# thermostat_sensor_esp32.net
KiCad netlist of a schematic drawn in EAGLE
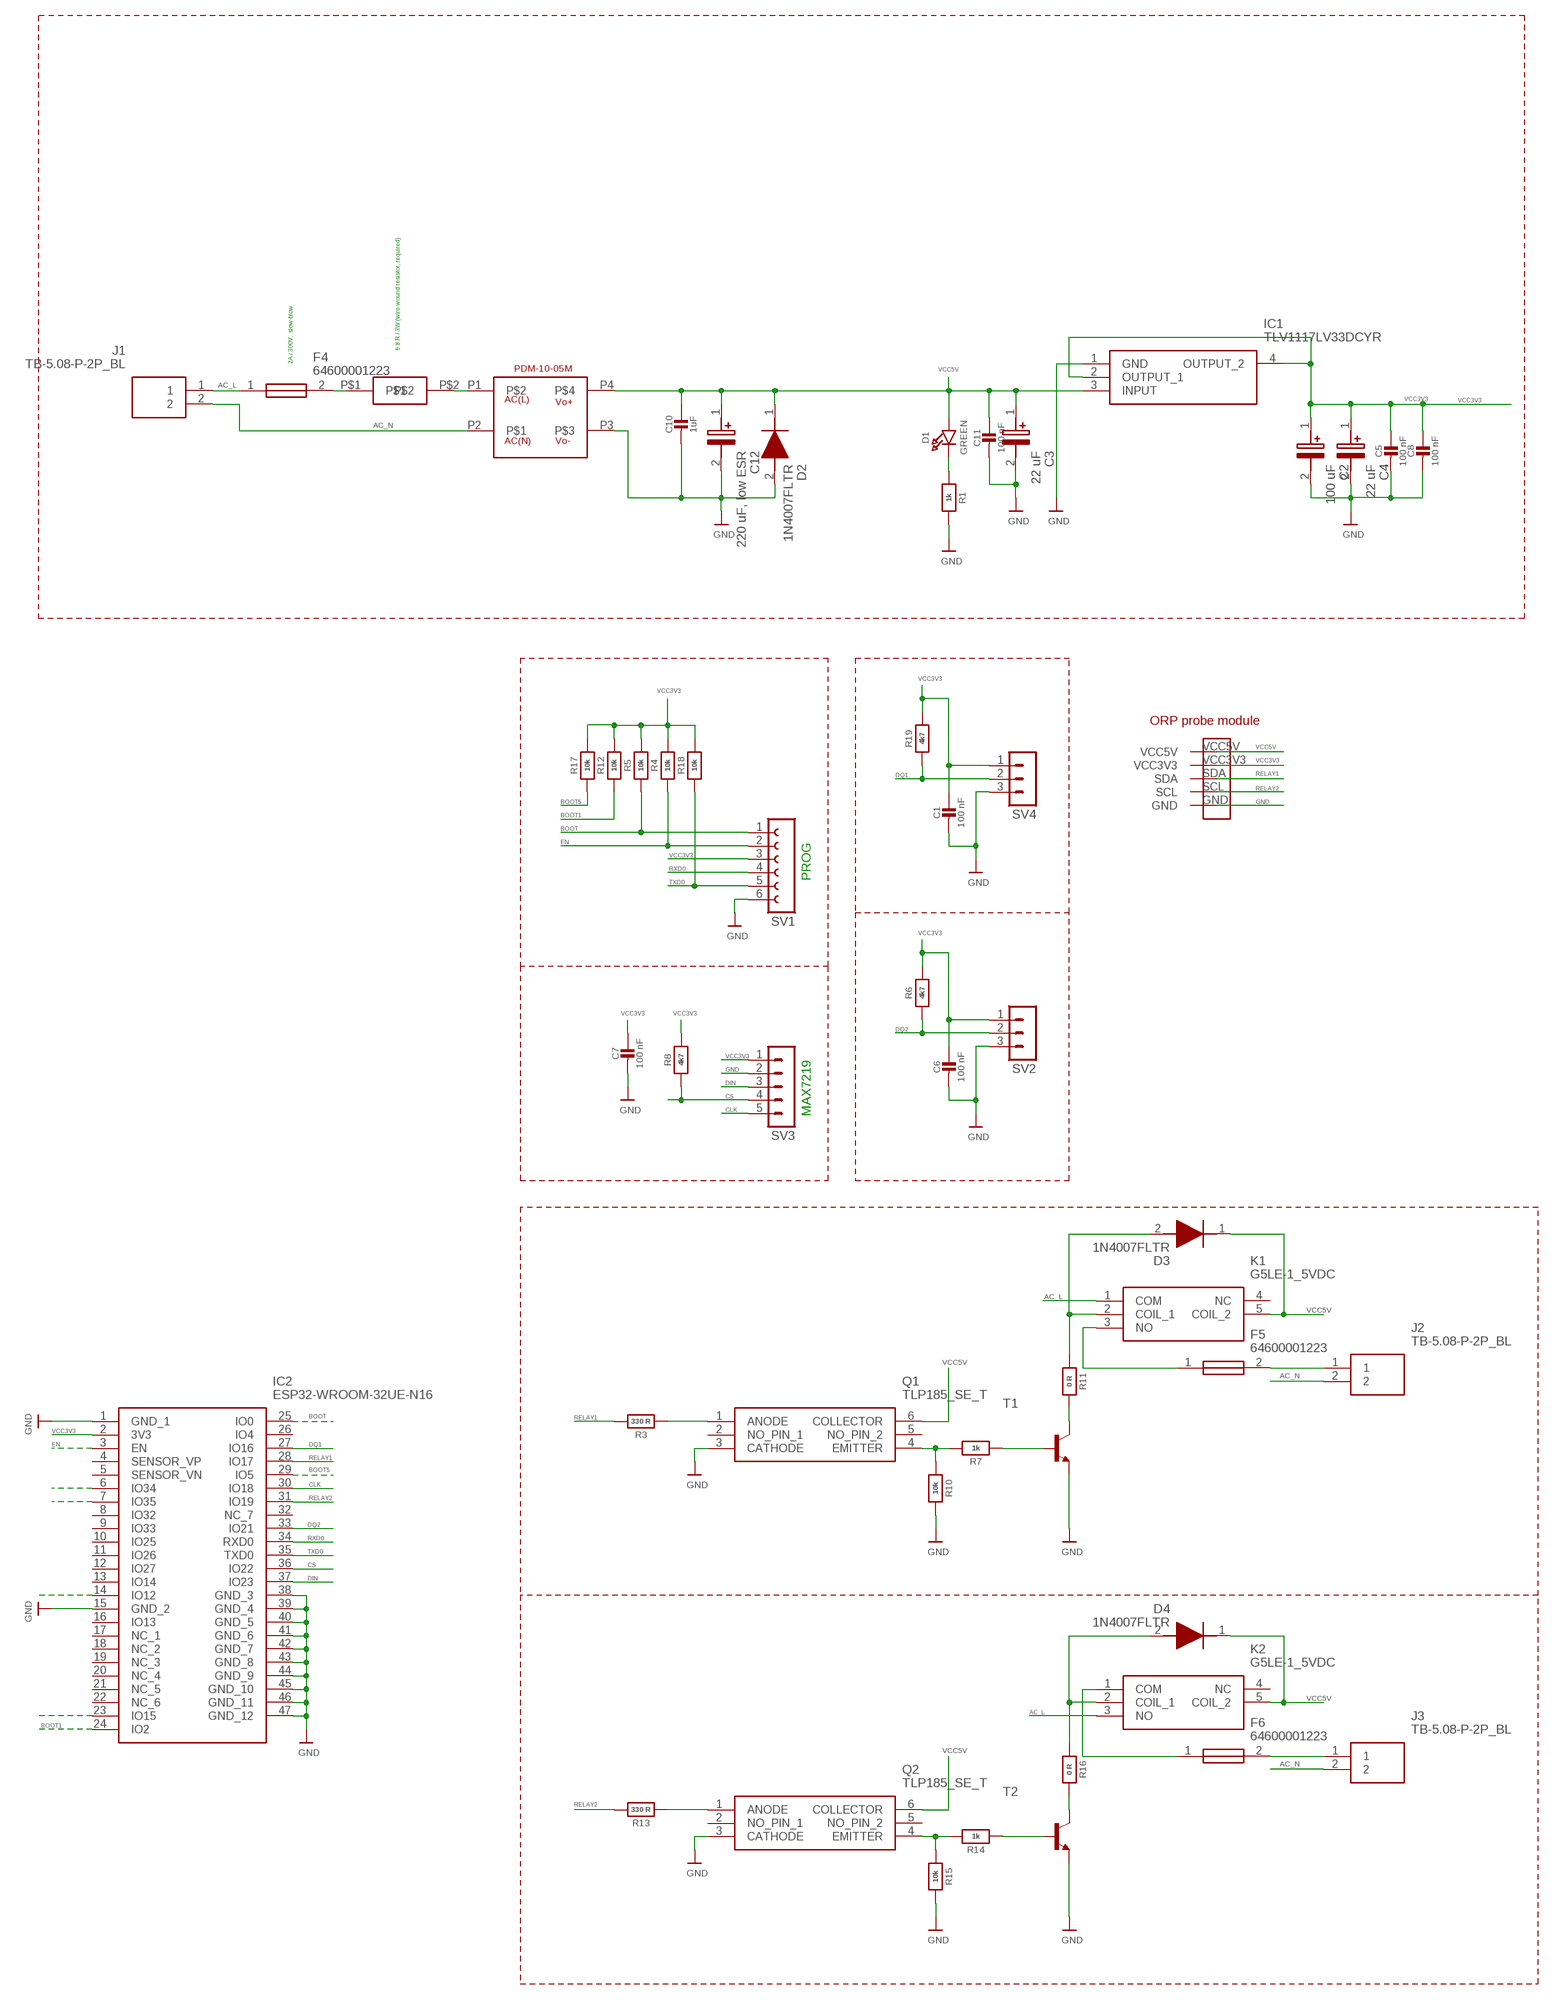
[diagram p0: schematic, sheet 1]

(export (version "E")
  (design (tool "Eeschema 10.0.6"))
  (components
    (comp (ref "C1")
      (value "100 nF")
      (footprint "eagle-import:_0603")
      (libsource (lib "eagle-import") (part "CAP_CERAMIC_0603"))
    )
    (comp (ref "C2")
      (value "100 uF")
      (footprint "eagle-import:CAPPM6032X280N")
      (fields (field (name "MANUFACTURER_PART_NUMBER") "293D107X9010C2TE3"))
      (libsource (lib "eagle-import") (part "293D107X9010C2TE3"))
    )
    (comp (ref "C3")
      (value "22 uF")
      (footprint "eagle-import:CAPPM3216X180N")
      (description "Solid Tantalum Surface Mount Chip Capacitors TANTAMOUNT(TM), Molded Case, Standard Industrial Grade")
      (fields
        (field (name "MANUFACTURER_PART_NUMBER") "293D226X9010A2TE3")
        (field (name "HEIGHT") "1.8mm")
        (field (name "MANUFACTURER_NAME") "Vishay")
        (field (name "MANUFACTURER_PART_NUMBER_1") "293D226X9010A2TE3")
      )
      (libsource (lib "eagle-import") (part "293D226X9010A2TE3"))
    )
    (comp (ref "C4")
      (value "22 uF")
      (footprint "eagle-import:CAPPM3216X180N")
      (description "Solid Tantalum Surface Mount Chip Capacitors TANTAMOUNT(TM), Molded Case, Standard Industrial Grade")
      (fields
        (field (name "MANUFACTURER_PART_NUMBER") "293D226X9010A2TE3")
        (field (name "HEIGHT") "1.8mm")
        (field (name "MANUFACTURER_NAME") "Vishay")
        (field (name "MANUFACTURER_PART_NUMBER_1") "293D226X9010A2TE3")
      )
      (libsource (lib "eagle-import") (part "293D226X9010A2TE3"))
    )
    (comp (ref "C5")
      (value "100 nF")
      (footprint "eagle-import:_0603")
      (libsource (lib "eagle-import") (part "CAP_CERAMIC_0603"))
    )
    (comp (ref "C6")
      (value "100 nF")
      (footprint "eagle-import:_0603")
      (libsource (lib "eagle-import") (part "CAP_CERAMIC_0603"))
    )
    (comp (ref "C7")
      (value "100 nF")
      (footprint "eagle-import:_0603")
      (libsource (lib "eagle-import") (part "CAP_CERAMIC_0603"))
    )
    (comp (ref "C8")
      (value "100 nF")
      (footprint "eagle-import:_0603")
      (libsource (lib "eagle-import") (part "CAP_CERAMIC_0603"))
    )
    (comp (ref "C10")
      (value "1uF")
      (footprint "eagle-import:0805-NO")
      (libsource (lib "eagle-import") (part "CAP_CERAMIC0805-NOOUTLINE"))
    )
    (comp (ref "C11")
      (value "100 nF")
      (footprint "eagle-import:_0603")
      (libsource (lib "eagle-import") (part "CAP_CERAMIC_0603"))
    )
    (comp (ref "C12")
      (value "220 uF, low ESR")
      (footprint "eagle-import:CAPPRD350W65D800H1300")
      (fields (field (name "MANUFACTURER_PART_NUMBER") "EEUFR1E221B"))
      (libsource (lib "eagle-import") (part "EEUFR1E221B"))
    )
    (comp (ref "D1")
      (value "GREEN")
      (footprint "eagle-import:CHIPLED_0805_NOOUTLINE")
      (libsource (lib "eagle-import") (part "LED0805_NOOUTLINE"))
    )
    (comp (ref "D2")
      (value "1N4007FLTR")
      (footprint "eagle-import:SODFL3718X140N")
      (libsource (lib "eagle-import") (part "1N4007FLTR"))
    )
    (comp (ref "D3")
      (value "1N4007FLTR")
      (footprint "eagle-import:SODFL3718X140N")
      (description "General Purpose Plastic Rectifier")
      (fields
        (field (name "HEIGHT") "1.4mm")
        (field (name "MANUFACTURER_NAME") "SMC Diode Solutions")
        (field (name "MANUFACTURER_PART_NUMBER") "1N4007FLTR")
      )
      (libsource (lib "eagle-import") (part "1N4007FLTR"))
    )
    (comp (ref "D4")
      (value "1N4007FLTR")
      (footprint "eagle-import:SODFL3718X140N")
      (description "General Purpose Plastic Rectifier")
      (fields
        (field (name "HEIGHT") "1.4mm")
        (field (name "MANUFACTURER_NAME") "SMC Diode Solutions")
        (field (name "MANUFACTURER_PART_NUMBER") "1N4007FLTR")
      )
      (libsource (lib "eagle-import") (part "1N4007FLTR"))
    )
    (comp (ref "F4")
      (value "64600001223")
      (footprint "eagle-import:64600001223")
      (libsource (lib "eagle-import") (part "64600001223"))
    )
    (comp (ref "F5")
      (value "64600001223")
      (footprint "eagle-import:64600001223")
      (libsource (lib "eagle-import") (part "64600001223"))
    )
    (comp (ref "F6")
      (value "64600001223")
      (footprint "eagle-import:64600001223")
      (libsource (lib "eagle-import") (part "64600001223"))
    )
    (comp (ref "IC1")
      (value "TLV1117LV33DCYR")
      (footprint "eagle-import:SOT230P700X180-4N")
      (libsource (lib "eagle-import") (part "TLV1117LV33DCYR"))
    )
    (comp (ref "IC2")
      (value "ESP32-WROOM-32UE-N16")
      (footprint "eagle-import:ESP32WROOM32UEN16")
      (libsource (lib "eagle-import") (part "ESP32-WROOM-32UE-N16"))
    )
    (comp (ref "J1")
      (value "TB-5.08-P-2P_BL")
      (footprint "eagle-import:TB508P2PBL")
      (fields (field (name "MANUFACTURER_PART_NUMBER") "TB-5.08-P-2P/BL"))
      (libsource (lib "eagle-import") (part "TB-5.08-P-2P_BL"))
    )
    (comp (ref "J2")
      (value "TB-5.08-P-2P_BL")
      (footprint "eagle-import:TB508P2PBL")
      (description "PCB terminal block; angled 90; 5.08mm; ways: 2; on PCBs; 1.5mm2")
      (fields
        (field (name "MANUFACTURER_PART_NUMBER") "TB-5.08-P-2P/BL")
        (field (name "HEIGHT") "10mm")
        (field (name "MANUFACTURER_NAME") "Ninigi")
        (field (name "MANUFACTURER_PART_NUMBER_1") "TB-5.08-P-2P/BL")
      )
      (libsource (lib "eagle-import") (part "TB-5.08-P-2P_BL"))
    )
    (comp (ref "J3")
      (value "TB-5.08-P-2P_BL")
      (footprint "eagle-import:TB508P2PBL")
      (description "PCB terminal block; angled 90; 5.08mm; ways: 2; on PCBs; 1.5mm2")
      (fields
        (field (name "MANUFACTURER_PART_NUMBER") "TB-5.08-P-2P/BL")
        (field (name "HEIGHT") "10mm")
        (field (name "MANUFACTURER_NAME") "Ninigi")
        (field (name "MANUFACTURER_PART_NUMBER_1") "TB-5.08-P-2P/BL")
      )
      (libsource (lib "eagle-import") (part "TB-5.08-P-2P_BL"))
    )
    (comp (ref "K1")
      (value "G5LE-1_5VDC")
      (footprint "eagle-import:G5LE15VDC")
      (fields (field (name "MANUFACTURER_PART_NUMBER") "G5LE-1 5VDC"))
      (libsource (lib "eagle-import") (part "G5LE-1_5VDC"))
    )
    (comp (ref "K2")
      (value "G5LE-1_5VDC")
      (footprint "eagle-import:G5LE15VDC")
      (fields (field (name "MANUFACTURER_PART_NUMBER") "G5LE-1 5VDC"))
      (libsource (lib "eagle-import") (part "G5LE-1_5VDC"))
    )
    (comp (ref "Q1")
      (value "TLP185_SE_T")
      (footprint "eagle-import:SOIC127P700X230-6N")
      (fields (field (name "MANUFACTURER_PART_NUMBER") "TLP185(SE(T"))
      (libsource (lib "eagle-import") (part "TLP185_SE_T"))
    )
    (comp (ref "Q2")
      (value "TLP185_SE_T")
      (footprint "eagle-import:SOIC127P700X230-6N")
      (fields (field (name "MANUFACTURER_PART_NUMBER") "TLP185(SE(T"))
      (libsource (lib "eagle-import") (part "TLP185_SE_T"))
    )
    (comp (ref "R1")
      (value "1k")
      (footprint "eagle-import:_0603")
      (libsource (lib "eagle-import") (part "RESISTOR_0603"))
    )
    (comp (ref "R3")
      (value "330 R")
      (footprint "eagle-import:_0603")
      (libsource (lib "eagle-import") (part "RESISTOR_0603"))
    )
    (comp (ref "R4")
      (value "10k")
      (footprint "eagle-import:_0603")
      (libsource (lib "eagle-import") (part "RESISTOR_0603"))
    )
    (comp (ref "R5")
      (value "10k")
      (footprint "eagle-import:_0603")
      (libsource (lib "eagle-import") (part "RESISTOR_0603"))
    )
    (comp (ref "R6")
      (value "4k7")
      (footprint "eagle-import:_0603")
      (libsource (lib "eagle-import") (part "RESISTOR_0603"))
    )
    (comp (ref "R7")
      (value "1k")
      (footprint "eagle-import:_0603")
      (libsource (lib "eagle-import") (part "RESISTOR_0603"))
    )
    (comp (ref "R8")
      (value "4k7")
      (footprint "eagle-import:_0603")
      (libsource (lib "eagle-import") (part "RESISTOR_0603"))
    )
    (comp (ref "R10")
      (value "10k")
      (footprint "eagle-import:_0603")
      (libsource (lib "eagle-import") (part "RESISTOR_0603"))
    )
    (comp (ref "R11")
      (value "0 R")
      (footprint "eagle-import:_0603")
      (libsource (lib "eagle-import") (part "RESISTOR_0603"))
    )
    (comp (ref "R12")
      (value "10k")
      (footprint "eagle-import:_0603")
      (libsource (lib "eagle-import") (part "RESISTOR_0603"))
    )
    (comp (ref "R13")
      (value "330 R")
      (footprint "eagle-import:_0603")
      (libsource (lib "eagle-import") (part "RESISTOR_0603"))
    )
    (comp (ref "R14")
      (value "1k")
      (footprint "eagle-import:_0603")
      (libsource (lib "eagle-import") (part "RESISTOR_0603"))
    )
    (comp (ref "R15")
      (value "10k")
      (footprint "eagle-import:_0603")
      (libsource (lib "eagle-import") (part "RESISTOR_0603"))
    )
    (comp (ref "R16")
      (value "0 R")
      (footprint "eagle-import:_0603")
      (libsource (lib "eagle-import") (part "RESISTOR_0603"))
    )
    (comp (ref "R17")
      (value "10k")
      (footprint "eagle-import:_0603")
      (libsource (lib "eagle-import") (part "RESISTOR_0603"))
    )
    (comp (ref "R18")
      (value "10k")
      (footprint "eagle-import:_0603")
      (libsource (lib "eagle-import") (part "RESISTOR_0603"))
    )
    (comp (ref "R19")
      (value "4k7")
      (footprint "eagle-import:_0603")
      (libsource (lib "eagle-import") (part "RESISTOR_0603"))
    )
    (comp (ref "SV1")
      (value "FE06-1")
      (footprint "eagle-import:FE06")
      (libsource (lib "eagle-import") (part "FE06-1"))
    )
    (comp (ref "SV2")
      (value "MA03-1")
      (footprint "eagle-import:MA03-1")
      (libsource (lib "eagle-import") (part "MA03-1"))
    )
    (comp (ref "SV3")
      (value "MA05-1")
      (footprint "eagle-import:MA05-1")
      (libsource (lib "eagle-import") (part "MA05-1"))
    )
    (comp (ref "SV4")
      (value "MA03-1")
      (footprint "eagle-import:MA03-1")
      (libsource (lib "eagle-import") (part "MA03-1"))
    )
    (comp (ref "T1")
      (value "BC817-16-NPN-SOT23-BEC")
      (footprint "eagle-import:SOT23-BEC")
      (libsource (lib "eagle-import") (part "-NPN-SOT23-BECBC817-16"))
    )
    (comp (ref "T2")
      (value "BC817-16-NPN-SOT23-BEC")
      (footprint "eagle-import:SOT23-BEC")
      (libsource (lib "eagle-import") (part "-NPN-SOT23-BECBC817-16"))
    )
    (comp (ref "U$1")
      (value "PDM-10-05M")
      (footprint "eagle-import:PDM-10-05M")
      (libsource (lib "eagle-import") (part "PDM-10-05M"))
    )
    (comp (ref "U$20")
      (value "6.8 R / 3W (wire-wound resistor, required)")
      (footprint "eagle-import:R_HIGH_POWER")
      (libsource (lib "eagle-import") (part "R_HIGH_POWER"))
    )
    (comp (ref "U$21")
      (value "ORP_PROBE")
      (footprint "eagle-import:ORP_PROBE")
      (libsource (lib "eagle-import") (part "ORP_PROBE"))
    )
  )
  (nets
    (net (code "1") (name "/AC_L") (class "Default")
      (node (ref "F4") (pin "1") (pinfunction "1_1") (pintype "bidirectional"))
      (node (ref "J1") (pin "1") (pinfunction "1_1") (pintype "bidirectional"))
      (node (ref "K1") (pin "1") (pinfunction "COM_1") (pintype "bidirectional"))
      (node (ref "K2") (pin "3") (pinfunction "NO_3") (pintype "bidirectional"))
    )
    (net (code "2") (name "/AC_N") (class "Default")
      (node (ref "J1") (pin "2") (pinfunction "2_2") (pintype "bidirectional"))
      (node (ref "J2") (pin "2") (pinfunction "2_2") (pintype "bidirectional"))
      (node (ref "J3") (pin "2") (pinfunction "2_2") (pintype "bidirectional"))
      (node (ref "U$1") (pin "P2") (pinfunction "P$1_P2") (pintype "bidirectional"))
    )
    (net (code "3") (name "/BOOT") (class "Default")
      (node (ref "IC2") (pin "25") (pinfunction "IO0_25") (pintype "bidirectional"))
      (node (ref "R5") (pin "1") (pinfunction "1_1") (pintype "passive"))
      (node (ref "SV1") (pin "1") (pinfunction "1_1") (pintype "passive"))
    )
    (net (code "4") (name "/BOOT1") (class "Default")
      (node (ref "IC2") (pin "24") (pinfunction "IO2_24") (pintype "bidirectional"))
      (node (ref "R12") (pin "1") (pinfunction "1_1") (pintype "passive"))
    )
    (net (code "5") (name "/BOOT5") (class "Default")
      (node (ref "IC2") (pin "29") (pinfunction "IO5_29") (pintype "bidirectional"))
      (node (ref "R17") (pin "1") (pinfunction "1_1") (pintype "passive"))
    )
    (net (code "6") (name "/CLK") (class "Default")
      (node (ref "IC2") (pin "30") (pinfunction "IO18_30") (pintype "bidirectional"))
      (node (ref "SV3") (pin "5") (pinfunction "5_5") (pintype "passive"))
    )
    (net (code "7") (name "/CS") (class "Default")
      (node (ref "IC2") (pin "36") (pinfunction "IO22_36") (pintype "bidirectional"))
      (node (ref "R8") (pin "1") (pinfunction "1_1") (pintype "passive"))
      (node (ref "SV3") (pin "4") (pinfunction "4_4") (pintype "passive"))
    )
    (net (code "8") (name "/DIN") (class "Default")
      (node (ref "IC2") (pin "37") (pinfunction "IO23_37") (pintype "bidirectional"))
      (node (ref "SV3") (pin "3") (pinfunction "3_3") (pintype "passive"))
    )
    (net (code "9") (name "/DQ1") (class "Default")
      (node (ref "IC2") (pin "27") (pinfunction "IO16_27") (pintype "bidirectional"))
      (node (ref "R19") (pin "1") (pinfunction "1_1") (pintype "passive"))
      (node (ref "SV4") (pin "2") (pinfunction "2_2") (pintype "passive"))
    )
    (net (code "10") (name "/DQ2") (class "Default")
      (node (ref "IC2") (pin "33") (pinfunction "IO21_33") (pintype "bidirectional"))
      (node (ref "R6") (pin "1") (pinfunction "1_1") (pintype "passive"))
      (node (ref "SV2") (pin "2") (pinfunction "2_2") (pintype "passive"))
    )
    (net (code "11") (name "/EN") (class "Default")
      (node (ref "IC2") (pin "3") (pinfunction "EN_3") (pintype "bidirectional"))
      (node (ref "R4") (pin "1") (pinfunction "1_1") (pintype "passive"))
      (node (ref "SV1") (pin "2") (pinfunction "2_2") (pintype "passive"))
    )
    (net (code "12") (name "/RELAY1") (class "Default")
      (node (ref "IC2") (pin "28") (pinfunction "IO17_28") (pintype "bidirectional"))
      (node (ref "R3") (pin "2") (pinfunction "2_2") (pintype "passive"))
      (node (ref "U$21") (pin "SDA") (pinfunction "SDA_SDA") (pintype "bidirectional"))
    )
    (net (code "13") (name "/RELAY2") (class "Default")
      (node (ref "IC2") (pin "31") (pinfunction "IO19_31") (pintype "bidirectional"))
      (node (ref "R13") (pin "2") (pinfunction "2_2") (pintype "passive"))
      (node (ref "U$21") (pin "SCL") (pinfunction "SCL_SCL") (pintype "bidirectional"))
    )
    (net (code "14") (name "/RXD0") (class "Default")
      (node (ref "IC2") (pin "34") (pinfunction "RXD0_34") (pintype "bidirectional"))
      (node (ref "SV1") (pin "4") (pinfunction "4_4") (pintype "passive"))
    )
    (net (code "15") (name "/TXD0") (class "Default")
      (node (ref "IC2") (pin "35") (pinfunction "TXD0_35") (pintype "bidirectional"))
      (node (ref "R18") (pin "1") (pinfunction "1_1") (pintype "passive"))
      (node (ref "SV1") (pin "5") (pinfunction "5_5") (pintype "passive"))
    )
    (net (code "16") (name "/VCC3V3") (class "Default")
      (node (ref "C1") (pin "1") (pinfunction "1_1") (pintype "passive"))
      (node (ref "C2") (pin "1") (pinfunction "+_1") (pintype "bidirectional"))
      (node (ref "C4") (pin "1") (pinfunction "+_1") (pintype "bidirectional"))
      (node (ref "C5") (pin "1") (pinfunction "1_1") (pintype "passive"))
      (node (ref "C6") (pin "1") (pinfunction "1_1") (pintype "passive"))
      (node (ref "C7") (pin "1") (pinfunction "1_1") (pintype "passive"))
      (node (ref "C8") (pin "1") (pinfunction "1_1") (pintype "passive"))
      (node (ref "IC1") (pin "2") (pinfunction "OUTPUT_1_2") (pintype "bidirectional"))
      (node (ref "IC1") (pin "4") (pinfunction "OUTPUT_2_4") (pintype "bidirectional"))
      (node (ref "IC2") (pin "2") (pinfunction "3V3_2") (pintype "bidirectional"))
      (node (ref "R12") (pin "2") (pinfunction "2_2") (pintype "passive"))
      (node (ref "R17") (pin "2") (pinfunction "2_2") (pintype "passive"))
      (node (ref "R18") (pin "2") (pinfunction "2_2") (pintype "passive"))
      (node (ref "R19") (pin "2") (pinfunction "2_2") (pintype "passive"))
      (node (ref "R4") (pin "2") (pinfunction "2_2") (pintype "passive"))
      (node (ref "R5") (pin "2") (pinfunction "2_2") (pintype "passive"))
      (node (ref "R6") (pin "2") (pinfunction "2_2") (pintype "passive"))
      (node (ref "R8") (pin "2") (pinfunction "2_2") (pintype "passive"))
      (node (ref "SV1") (pin "3") (pinfunction "3_3") (pintype "passive"))
      (node (ref "SV2") (pin "1") (pinfunction "1_1") (pintype "passive"))
      (node (ref "SV3") (pin "1") (pinfunction "1_1") (pintype "passive"))
      (node (ref "SV4") (pin "1") (pinfunction "1_1") (pintype "passive"))
      (node (ref "U$21") (pin "VCC3V3") (pinfunction "VCC3V3_VCC3V3") (pintype "bidirectional"))
    )
    (net (code "17") (name "/VCC5V") (class "Default")
      (node (ref "C10") (pin "1") (pinfunction "1_1") (pintype "passive"))
      (node (ref "C11") (pin "1") (pinfunction "1_1") (pintype "passive"))
      (node (ref "C12") (pin "1") (pinfunction "+_1") (pintype "bidirectional"))
      (node (ref "C3") (pin "1") (pinfunction "+_1") (pintype "bidirectional"))
      (node (ref "D1") (pin "A") (pinfunction "A_A") (pintype "passive"))
      (node (ref "D2") (pin "1") (pinfunction "K_1") (pintype "bidirectional"))
      (node (ref "D3") (pin "1") (pinfunction "K_1") (pintype "bidirectional"))
      (node (ref "D4") (pin "1") (pinfunction "K_1") (pintype "bidirectional"))
      (node (ref "IC1") (pin "3") (pinfunction "INPUT_3") (pintype "bidirectional"))
      (node (ref "K1") (pin "5") (pinfunction "COIL_2_5") (pintype "bidirectional"))
      (node (ref "K2") (pin "5") (pinfunction "COIL_2_5") (pintype "bidirectional"))
      (node (ref "Q1") (pin "6") (pinfunction "COLLECTOR_6") (pintype "bidirectional"))
      (node (ref "Q2") (pin "6") (pinfunction "COLLECTOR_6") (pintype "bidirectional"))
      (node (ref "U$1") (pin "P4") (pinfunction "P$4_P4") (pintype "bidirectional"))
      (node (ref "U$21") (pin "VCC5V") (pinfunction "VCC5V_VCC5V") (pintype "bidirectional"))
    )
    (net (code "18") (name "GND") (class "Default")
      (node (ref "C1") (pin "2") (pinfunction "2_2") (pintype "passive"))
      (node (ref "C10") (pin "2") (pinfunction "2_2") (pintype "passive"))
      (node (ref "C11") (pin "2") (pinfunction "2_2") (pintype "passive"))
      (node (ref "C12") (pin "2") (pinfunction "-_2") (pintype "bidirectional"))
      (node (ref "C2") (pin "2") (pinfunction "-_2") (pintype "bidirectional"))
      (node (ref "C3") (pin "2") (pinfunction "-_2") (pintype "bidirectional"))
      (node (ref "C4") (pin "2") (pinfunction "-_2") (pintype "bidirectional"))
      (node (ref "C5") (pin "2") (pinfunction "2_2") (pintype "passive"))
      (node (ref "C6") (pin "2") (pinfunction "2_2") (pintype "passive"))
      (node (ref "C7") (pin "2") (pinfunction "2_2") (pintype "passive"))
      (node (ref "C8") (pin "2") (pinfunction "2_2") (pintype "passive"))
      (node (ref "D2") (pin "2") (pinfunction "A_2") (pintype "bidirectional"))
      (node (ref "IC1") (pin "1") (pinfunction "GND_1") (pintype "bidirectional"))
      (node (ref "IC2") (pin "1") (pinfunction "GND_1_1") (pintype "bidirectional"))
      (node (ref "IC2") (pin "15") (pinfunction "GND_2_15") (pintype "bidirectional"))
      (node (ref "IC2") (pin "38") (pinfunction "GND_3_38") (pintype "bidirectional"))
      (node (ref "IC2") (pin "39") (pinfunction "GND_4_39") (pintype "bidirectional"))
      (node (ref "IC2") (pin "40") (pinfunction "GND_5_40") (pintype "bidirectional"))
      (node (ref "IC2") (pin "41") (pinfunction "GND_6_41") (pintype "bidirectional"))
      (node (ref "IC2") (pin "42") (pinfunction "GND_7_42") (pintype "bidirectional"))
      (node (ref "IC2") (pin "43") (pinfunction "GND_8_43") (pintype "bidirectional"))
      (node (ref "IC2") (pin "44") (pinfunction "GND_9_44") (pintype "bidirectional"))
      (node (ref "IC2") (pin "45") (pinfunction "GND_10_45") (pintype "bidirectional"))
      (node (ref "IC2") (pin "46") (pinfunction "GND_11_46") (pintype "bidirectional"))
      (node (ref "IC2") (pin "47") (pinfunction "GND_12_47") (pintype "bidirectional"))
      (node (ref "Q1") (pin "3") (pinfunction "CATHODE_3") (pintype "bidirectional"))
      (node (ref "Q2") (pin "3") (pinfunction "CATHODE_3") (pintype "bidirectional"))
      (node (ref "R1") (pin "2") (pinfunction "2_2") (pintype "passive"))
      (node (ref "R10") (pin "2") (pinfunction "2_2") (pintype "passive"))
      (node (ref "R15") (pin "2") (pinfunction "2_2") (pintype "passive"))
      (node (ref "SV1") (pin "6") (pinfunction "6_6") (pintype "passive"))
      (node (ref "SV2") (pin "3") (pinfunction "3_3") (pintype "passive"))
      (node (ref "SV3") (pin "2") (pinfunction "2_2") (pintype "passive"))
      (node (ref "SV4") (pin "3") (pinfunction "3_3") (pintype "passive"))
      (node (ref "T1") (pin "E") (pinfunction "E_E") (pintype "passive"))
      (node (ref "T2") (pin "E") (pinfunction "E_E") (pintype "passive"))
      (node (ref "U$1") (pin "P3") (pinfunction "P$3_P3") (pintype "bidirectional"))
      (node (ref "U$21") (pin "GND") (pinfunction "GND_GND") (pintype "bidirectional"))
    )
    (net (code "19") (name "Net-(D1-PadC)") (class "Default")
      (node (ref "D1") (pin "C") (pinfunction "C_C") (pintype "passive"))
      (node (ref "R1") (pin "1") (pinfunction "1_1") (pintype "passive"))
    )
    (net (code "20") (name "Net-(D3-A)") (class "Default")
      (node (ref "D3") (pin "2") (pinfunction "A_2") (pintype "bidirectional"))
      (node (ref "K1") (pin "2") (pinfunction "COIL_1_2") (pintype "bidirectional"))
      (node (ref "R11") (pin "1") (pinfunction "1_1") (pintype "passive"))
    )
    (net (code "21") (name "Net-(D4-A)") (class "Default")
      (node (ref "D4") (pin "2") (pinfunction "A_2") (pintype "bidirectional"))
      (node (ref "K2") (pin "2") (pinfunction "COIL_1_2") (pintype "bidirectional"))
      (node (ref "R16") (pin "1") (pinfunction "1_1") (pintype "passive"))
    )
    (net (code "22") (name "Net-(F4-Pad2)") (class "Default")
      (node (ref "F4") (pin "2") (pinfunction "2_2") (pintype "bidirectional"))
      (node (ref "U$20") (pin "P$1") (pinfunction "P$1_P$1") (pintype "bidirectional"))
    )
    (net (code "23") (name "Net-(F5-Pad2)") (class "Default")
      (node (ref "F5") (pin "2") (pinfunction "2_2") (pintype "bidirectional"))
      (node (ref "J2") (pin "1") (pinfunction "1_1") (pintype "bidirectional"))
    )
    (net (code "24") (name "Net-(F6-Pad2)") (class "Default")
      (node (ref "F6") (pin "2") (pinfunction "2_2") (pintype "bidirectional"))
      (node (ref "J3") (pin "1") (pinfunction "1_1") (pintype "bidirectional"))
    )
    (net (code "25") (name "Net-(K1-NO)") (class "Default")
      (node (ref "F5") (pin "1") (pinfunction "1_1") (pintype "bidirectional"))
      (node (ref "K1") (pin "3") (pinfunction "NO_3") (pintype "bidirectional"))
    )
    (net (code "26") (name "Net-(K2-COM)") (class "Default")
      (node (ref "F6") (pin "1") (pinfunction "1_1") (pintype "bidirectional"))
      (node (ref "K2") (pin "1") (pinfunction "COM_1") (pintype "bidirectional"))
    )
    (net (code "27") (name "Net-(Q1-ANODE)") (class "Default")
      (node (ref "Q1") (pin "1") (pinfunction "ANODE_1") (pintype "bidirectional"))
      (node (ref "R3") (pin "1") (pinfunction "1_1") (pintype "passive"))
    )
    (net (code "28") (name "Net-(Q1-EMITTER)") (class "Default")
      (node (ref "Q1") (pin "4") (pinfunction "EMITTER_4") (pintype "bidirectional"))
      (node (ref "R10") (pin "1") (pinfunction "1_1") (pintype "passive"))
      (node (ref "R7") (pin "2") (pinfunction "2_2") (pintype "passive"))
    )
    (net (code "29") (name "Net-(Q2-ANODE)") (class "Default")
      (node (ref "Q2") (pin "1") (pinfunction "ANODE_1") (pintype "bidirectional"))
      (node (ref "R13") (pin "1") (pinfunction "1_1") (pintype "passive"))
    )
    (net (code "30") (name "Net-(Q2-EMITTER)") (class "Default")
      (node (ref "Q2") (pin "4") (pinfunction "EMITTER_4") (pintype "bidirectional"))
      (node (ref "R14") (pin "2") (pinfunction "2_2") (pintype "passive"))
      (node (ref "R15") (pin "1") (pinfunction "1_1") (pintype "passive"))
    )
    (net (code "31") (name "Net-(R7-Pad1)") (class "Default")
      (node (ref "R7") (pin "1") (pinfunction "1_1") (pintype "passive"))
      (node (ref "T1") (pin "B") (pinfunction "B_B") (pintype "passive"))
    )
    (net (code "32") (name "Net-(R11-Pad2)") (class "Default")
      (node (ref "R11") (pin "2") (pinfunction "2_2") (pintype "passive"))
      (node (ref "T1") (pin "C") (pinfunction "C_C") (pintype "passive"))
    )
    (net (code "33") (name "Net-(R14-Pad1)") (class "Default")
      (node (ref "R14") (pin "1") (pinfunction "1_1") (pintype "passive"))
      (node (ref "T2") (pin "B") (pinfunction "B_B") (pintype "passive"))
    )
    (net (code "34") (name "Net-(R16-Pad2)") (class "Default")
      (node (ref "R16") (pin "2") (pinfunction "2_2") (pintype "passive"))
      (node (ref "T2") (pin "C") (pinfunction "C_C") (pintype "passive"))
    )
    (net (code "35") (name "Net-(U$1-P$2)") (class "Default")
      (node (ref "U$1") (pin "P1") (pinfunction "P$2_P1") (pintype "bidirectional"))
      (node (ref "U$20") (pin "P$2") (pinfunction "P$2_P$2") (pintype "bidirectional"))
    )
    (net (code "36") (name "unconnected-(IC2-IO4-Pad26)") (class "Default")
      (node (ref "IC2") (pin "26") (pinfunction "IO4_26") (pintype "bidirectional"))
    )
    (net (code "37") (name "unconnected-(IC2-IO12-Pad14)") (class "Default")
      (node (ref "IC2") (pin "14") (pinfunction "IO12_14") (pintype "bidirectional"))
    )
    (net (code "38") (name "unconnected-(IC2-IO13-Pad16)") (class "Default")
      (node (ref "IC2") (pin "16") (pinfunction "IO13_16") (pintype "bidirectional"))
    )
    (net (code "39") (name "unconnected-(IC2-IO14-Pad13)") (class "Default")
      (node (ref "IC2") (pin "13") (pinfunction "IO14_13") (pintype "bidirectional"))
    )
    (net (code "40") (name "unconnected-(IC2-IO15-Pad23)") (class "Default")
      (node (ref "IC2") (pin "23") (pinfunction "IO15_23") (pintype "bidirectional"))
    )
    (net (code "41") (name "unconnected-(IC2-IO25-Pad10)") (class "Default")
      (node (ref "IC2") (pin "10") (pinfunction "IO25_10") (pintype "bidirectional"))
    )
    (net (code "42") (name "unconnected-(IC2-IO26-Pad11)") (class "Default")
      (node (ref "IC2") (pin "11") (pinfunction "IO26_11") (pintype "bidirectional"))
    )
    (net (code "43") (name "unconnected-(IC2-IO27-Pad12)") (class "Default")
      (node (ref "IC2") (pin "12") (pinfunction "IO27_12") (pintype "bidirectional"))
    )
    (net (code "44") (name "unconnected-(IC2-IO32-Pad8)") (class "Default")
      (node (ref "IC2") (pin "8") (pinfunction "IO32_8") (pintype "bidirectional"))
    )
    (net (code "45") (name "unconnected-(IC2-IO33-Pad9)") (class "Default")
      (node (ref "IC2") (pin "9") (pinfunction "IO33_9") (pintype "bidirectional"))
    )
    (net (code "46") (name "unconnected-(IC2-IO34-Pad6)") (class "Default")
      (node (ref "IC2") (pin "6") (pinfunction "IO34_6") (pintype "bidirectional"))
    )
    (net (code "47") (name "unconnected-(IC2-IO35-Pad7)") (class "Default")
      (node (ref "IC2") (pin "7") (pinfunction "IO35_7") (pintype "bidirectional"))
    )
    (net (code "48") (name "unconnected-(IC2-NC_1-Pad17)") (class "Default")
      (node (ref "IC2") (pin "17") (pinfunction "NC_1_17") (pintype "bidirectional"))
    )
    (net (code "49") (name "unconnected-(IC2-NC_2-Pad18)") (class "Default")
      (node (ref "IC2") (pin "18") (pinfunction "NC_2_18") (pintype "bidirectional"))
    )
    (net (code "50") (name "unconnected-(IC2-NC_3-Pad19)") (class "Default")
      (node (ref "IC2") (pin "19") (pinfunction "NC_3_19") (pintype "bidirectional"))
    )
    (net (code "51") (name "unconnected-(IC2-NC_4-Pad20)") (class "Default")
      (node (ref "IC2") (pin "20") (pinfunction "NC_4_20") (pintype "bidirectional"))
    )
    (net (code "52") (name "unconnected-(IC2-NC_5-Pad21)") (class "Default")
      (node (ref "IC2") (pin "21") (pinfunction "NC_5_21") (pintype "bidirectional"))
    )
    (net (code "53") (name "unconnected-(IC2-NC_6-Pad22)") (class "Default")
      (node (ref "IC2") (pin "22") (pinfunction "NC_6_22") (pintype "bidirectional"))
    )
    (net (code "54") (name "unconnected-(IC2-NC_7-Pad32)") (class "Default")
      (node (ref "IC2") (pin "32") (pinfunction "NC_7_32") (pintype "bidirectional"))
    )
    (net (code "55") (name "unconnected-(IC2-SENSOR_VN-Pad5)") (class "Default")
      (node (ref "IC2") (pin "5") (pinfunction "SENSOR_VN_5") (pintype "bidirectional"))
    )
    (net (code "56") (name "unconnected-(IC2-SENSOR_VP-Pad4)") (class "Default")
      (node (ref "IC2") (pin "4") (pinfunction "SENSOR_VP_4") (pintype "bidirectional"))
    )
    (net (code "57") (name "unconnected-(K1-NC-Pad4)") (class "Default")
      (node (ref "K1") (pin "4") (pinfunction "NC_4") (pintype "no_connect"))
    )
    (net (code "58") (name "unconnected-(K2-NC-Pad4)") (class "Default")
      (node (ref "K2") (pin "4") (pinfunction "NC_4") (pintype "no_connect"))
    )
    (net (code "59") (name "unconnected-(Q1-NO_PIN_1-Pad2)") (class "Default")
      (node (ref "Q1") (pin "2") (pinfunction "NO_PIN_1_2") (pintype "bidirectional"))
    )
    (net (code "60") (name "unconnected-(Q1-NO_PIN_2-Pad5)") (class "Default")
      (node (ref "Q1") (pin "5") (pinfunction "NO_PIN_2_5") (pintype "bidirectional"))
    )
    (net (code "61") (name "unconnected-(Q2-NO_PIN_1-Pad2)") (class "Default")
      (node (ref "Q2") (pin "2") (pinfunction "NO_PIN_1_2") (pintype "bidirectional"))
    )
    (net (code "62") (name "unconnected-(Q2-NO_PIN_2-Pad5)") (class "Default")
      (node (ref "Q2") (pin "5") (pinfunction "NO_PIN_2_5") (pintype "bidirectional"))
    )
  )
)
